# LCD.net
KiCad netlist of a schematic drawn in Altium Designer
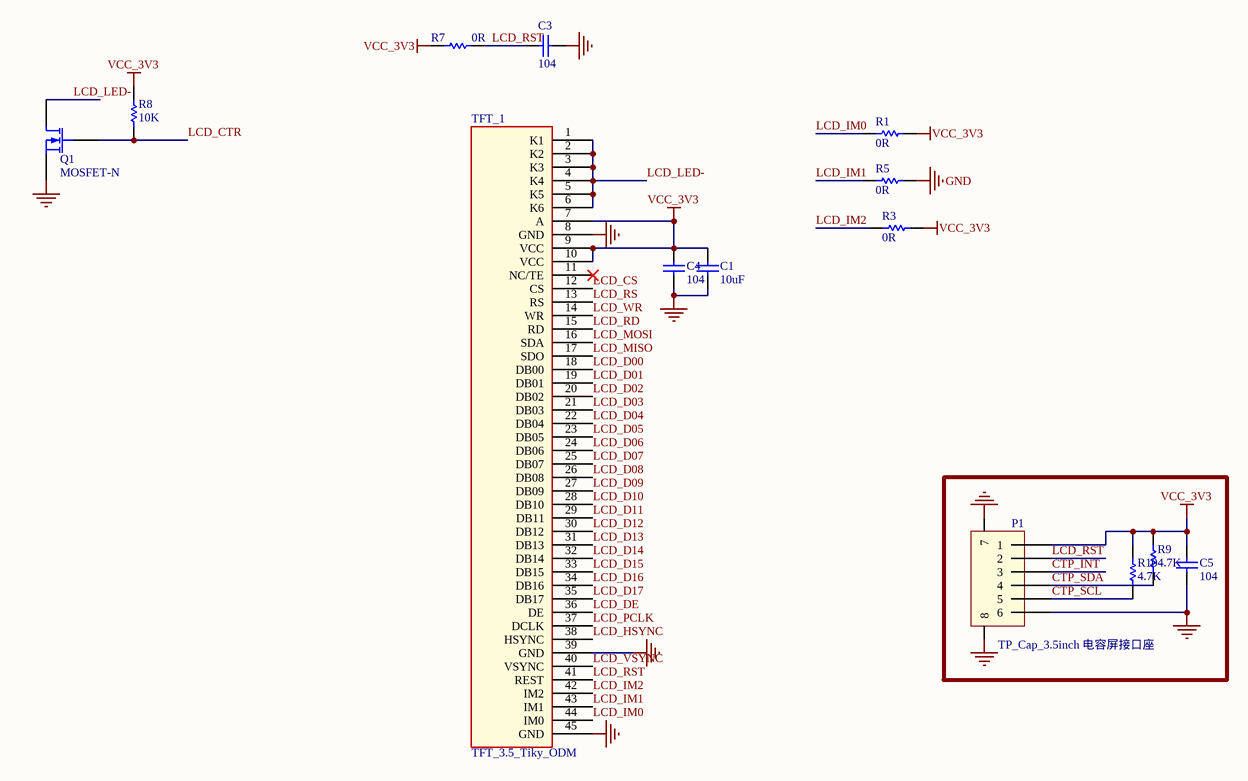
[diagram p0: LCD.SchDoc]

(export (version "E")
  (design (tool "Eeschema 10.0.6"))
  (components
    (comp (ref "C1")
      (value "10uF")
      (footprint "C 0603")
      (description "Capacitor")
      (libsource (lib "Miscellaneous Devices") (part "Cap"))
    )
    (comp (ref "C3") (value "104") (footprint "C 0603") (libsource (lib "Sheet") (part "CAP")))
    (comp (ref "C4")
      (value "104")
      (footprint "C 0603")
      (description "Capacitor")
      (libsource (lib "Miscellaneous Devices") (part "Cap"))
    )
    (comp (ref "C5")
      (value "104")
      (footprint "C 0603")
      (description "Capacitor")
      (libsource (lib "Miscellaneous Devices") (part "Cap"))
    )
    (comp (ref "P1")
      (value "TP_Cap_3.5inch 电容屏接口座")
      (footprint "TP_Cap_3.5inch")
      (libsource (lib "Tiky") (part "BHEADSMD1x6"))
    )
    (comp (ref "Q1") (value "MOSFET-N") (footprint "SOT-23") (libsource (lib "Tiky") (part "MOSFET-N")))
    (comp (ref "R1") (value "0R") (footprint "R 0603") (libsource (lib "Sheet") (part "RES")))
    (comp (ref "R3") (value "0R") (footprint "R 0603") (libsource (lib "Sheet") (part "RES")))
    (comp (ref "R5") (value "0R") (footprint "R 0603") (libsource (lib "Sheet") (part "RES")))
    (comp (ref "R7") (value "0R") (footprint "R 0603") (libsource (lib "Sheet") (part "RES")))
    (comp (ref "R8") (value "10K") (footprint "R 0603") (libsource (lib "Sheet") (part "RES")))
    (comp (ref "R9") (value "4.7K") (footprint "R 0603") (libsource (lib "Sheet") (part "RES")))
    (comp (ref "R10") (value "4.7K") (footprint "R 0603") (libsource (lib "Sheet") (part "RES")))
    (comp (ref "TFT_1")
      (value "TFT_3.5_Tiky_ODM")
      (footprint "TFT_3.5_TIKY_ODM")
      (libsource (lib "Tiky") (part "TFT_3.5_Tiky_ODM"))
    )
  )
  (nets
    (net (code "1") (name "/CTP_INT") (class "Default")
      (node (ref "P1") (pin "3") (pinfunction "3_3") (pintype "passive"))
    )
    (net (code "2") (name "/CTP_SCL") (class "Default")
      (node (ref "P1") (pin "5") (pinfunction "5_5") (pintype "passive"))
      (node (ref "R10") (pin "1") (pinfunction "1_1") (pintype "passive"))
    )
    (net (code "3") (name "/CTP_SDA") (class "Default")
      (node (ref "P1") (pin "4") (pinfunction "4_4") (pintype "passive"))
      (node (ref "R9") (pin "1") (pinfunction "1_1") (pintype "passive"))
    )
    (net (code "4") (name "/LCD_CS") (class "Default")
      (node (ref "TFT_1") (pin "12") (pinfunction "CS_12") (pintype "passive"))
    )
    (net (code "5") (name "/LCD_CTR") (class "Default")
      (node (ref "Q1") (pin "1") (pinfunction "G_1") (pintype "passive"))
      (node (ref "R8") (pin "1") (pinfunction "1_1") (pintype "passive"))
    )
    (net (code "6") (name "/LCD_D00") (class "Default")
      (node (ref "TFT_1") (pin "18") (pinfunction "DB00_18") (pintype "passive"))
    )
    (net (code "7") (name "/LCD_D01") (class "Default")
      (node (ref "TFT_1") (pin "19") (pinfunction "DB01_19") (pintype "passive"))
    )
    (net (code "8") (name "/LCD_D02") (class "Default")
      (node (ref "TFT_1") (pin "20") (pinfunction "DB02_20") (pintype "passive"))
    )
    (net (code "9") (name "/LCD_D03") (class "Default")
      (node (ref "TFT_1") (pin "21") (pinfunction "DB03_21") (pintype "passive"))
    )
    (net (code "10") (name "/LCD_D04") (class "Default")
      (node (ref "TFT_1") (pin "22") (pinfunction "DB04_22") (pintype "passive"))
    )
    (net (code "11") (name "/LCD_D05") (class "Default")
      (node (ref "TFT_1") (pin "23") (pinfunction "DB05_23") (pintype "passive"))
    )
    (net (code "12") (name "/LCD_D06") (class "Default")
      (node (ref "TFT_1") (pin "24") (pinfunction "DB06_24") (pintype "passive"))
    )
    (net (code "13") (name "/LCD_D07") (class "Default")
      (node (ref "TFT_1") (pin "25") (pinfunction "DB07_25") (pintype "passive"))
    )
    (net (code "14") (name "/LCD_D08") (class "Default")
      (node (ref "TFT_1") (pin "26") (pinfunction "DB08_26") (pintype "passive"))
    )
    (net (code "15") (name "/LCD_D09") (class "Default")
      (node (ref "TFT_1") (pin "27") (pinfunction "DB09_27") (pintype "passive"))
    )
    (net (code "16") (name "/LCD_D10") (class "Default")
      (node (ref "TFT_1") (pin "28") (pinfunction "DB10_28") (pintype "passive"))
    )
    (net (code "17") (name "/LCD_D11") (class "Default")
      (node (ref "TFT_1") (pin "29") (pinfunction "DB11_29") (pintype "passive"))
    )
    (net (code "18") (name "/LCD_D12") (class "Default")
      (node (ref "TFT_1") (pin "30") (pinfunction "DB12_30") (pintype "passive"))
    )
    (net (code "19") (name "/LCD_D13") (class "Default")
      (node (ref "TFT_1") (pin "31") (pinfunction "DB13_31") (pintype "passive"))
    )
    (net (code "20") (name "/LCD_D14") (class "Default")
      (node (ref "TFT_1") (pin "32") (pinfunction "DB14_32") (pintype "passive"))
    )
    (net (code "21") (name "/LCD_D15") (class "Default")
      (node (ref "TFT_1") (pin "33") (pinfunction "DB15_33") (pintype "passive"))
    )
    (net (code "22") (name "/LCD_D16") (class "Default")
      (node (ref "TFT_1") (pin "34") (pinfunction "DB16_34") (pintype "passive"))
    )
    (net (code "23") (name "/LCD_D17") (class "Default")
      (node (ref "TFT_1") (pin "35") (pinfunction "DB17_35") (pintype "passive"))
    )
    (net (code "24") (name "/LCD_DE") (class "Default")
      (node (ref "TFT_1") (pin "36") (pinfunction "DE_36") (pintype "passive"))
    )
    (net (code "25") (name "/LCD_HSYNC") (class "Default")
      (node (ref "TFT_1") (pin "38") (pinfunction "HSYNC_38") (pintype "passive"))
    )
    (net (code "26") (name "/LCD_IM0") (class "Default")
      (node (ref "R1") (pin "1") (pinfunction "1_1") (pintype "passive"))
      (node (ref "TFT_1") (pin "44") (pinfunction "IM0_44") (pintype "passive"))
    )
    (net (code "27") (name "/LCD_IM1") (class "Default")
      (node (ref "R5") (pin "1") (pinfunction "1_1") (pintype "passive"))
      (node (ref "TFT_1") (pin "43") (pinfunction "IM1_43") (pintype "passive"))
    )
    (net (code "28") (name "/LCD_IM2") (class "Default")
      (node (ref "R3") (pin "1") (pinfunction "1_1") (pintype "passive"))
      (node (ref "TFT_1") (pin "42") (pinfunction "IM2_42") (pintype "passive"))
    )
    (net (code "29") (name "/LCD_LED-") (class "Default")
      (node (ref "Q1") (pin "3") (pinfunction "D_3") (pintype "passive"))
      (node (ref "TFT_1") (pin "1") (pinfunction "K1_1") (pintype "passive"))
      (node (ref "TFT_1") (pin "2") (pinfunction "K2_2") (pintype "passive"))
      (node (ref "TFT_1") (pin "3") (pinfunction "K3_3") (pintype "passive"))
      (node (ref "TFT_1") (pin "4") (pinfunction "K4_4") (pintype "passive"))
      (node (ref "TFT_1") (pin "5") (pinfunction "K5_5") (pintype "passive"))
      (node (ref "TFT_1") (pin "6") (pinfunction "K6_6") (pintype "passive"))
    )
    (net (code "30") (name "/LCD_MISO") (class "Default")
      (node (ref "TFT_1") (pin "17") (pinfunction "SDO_17") (pintype "passive"))
    )
    (net (code "31") (name "/LCD_MOSI") (class "Default")
      (node (ref "TFT_1") (pin "16") (pinfunction "SDA_16") (pintype "passive"))
    )
    (net (code "32") (name "/LCD_PCLK") (class "Default")
      (node (ref "TFT_1") (pin "37") (pinfunction "DCLK_37") (pintype "passive"))
    )
    (net (code "33") (name "/LCD_RD") (class "Default")
      (node (ref "TFT_1") (pin "15") (pinfunction "RD_15") (pintype "passive"))
    )
    (net (code "34") (name "/LCD_RS") (class "Default")
      (node (ref "TFT_1") (pin "13") (pinfunction "RS_13") (pintype "passive"))
    )
    (net (code "35") (name "/LCD_RST") (class "Default")
      (node (ref "C3") (pin "2") (pinfunction "2_2") (pintype "passive"))
      (node (ref "P1") (pin "2") (pinfunction "2_2") (pintype "passive"))
      (node (ref "R7") (pin "2") (pinfunction "2_2") (pintype "passive"))
      (node (ref "TFT_1") (pin "41") (pinfunction "REST_41") (pintype "passive"))
    )
    (net (code "36") (name "/LCD_VSYNC") (class "Default")
      (node (ref "TFT_1") (pin "40") (pinfunction "VSYNC_40") (pintype "passive"))
    )
    (net (code "37") (name "/LCD_WR") (class "Default")
      (node (ref "TFT_1") (pin "14") (pinfunction "WR_14") (pintype "passive"))
    )
    (net (code "38") (name "GND") (class "Default")
      (node (ref "C1") (pin "2") (pinfunction "2_2") (pintype "passive"))
      (node (ref "C3") (pin "1") (pinfunction "1_1") (pintype "passive"))
      (node (ref "C4") (pin "2") (pinfunction "2_2") (pintype "passive"))
      (node (ref "C5") (pin "2") (pinfunction "2_2") (pintype "passive"))
      (node (ref "P1") (pin "6") (pinfunction "6_6") (pintype "passive"))
      (node (ref "P1") (pin "7") (pinfunction "7_7") (pintype "passive"))
      (node (ref "P1") (pin "8") (pinfunction "8_8") (pintype "passive"))
      (node (ref "Q1") (pin "2") (pinfunction "S_2") (pintype "passive"))
      (node (ref "R5") (pin "2") (pinfunction "2_2") (pintype "passive"))
      (node (ref "TFT_1") (pin "39") (pinfunction "GND_39") (pintype "passive"))
      (node (ref "TFT_1") (pin "45") (pinfunction "GND_45") (pintype "passive"))
      (node (ref "TFT_1") (pin "8") (pinfunction "GND_8") (pintype "passive"))
    )
    (net (code "39") (name "VCC_3V3") (class "Default")
      (node (ref "C1") (pin "1") (pinfunction "1_1") (pintype "passive"))
      (node (ref "C4") (pin "1") (pinfunction "1_1") (pintype "passive"))
      (node (ref "C5") (pin "1") (pinfunction "1_1") (pintype "passive"))
      (node (ref "P1") (pin "1") (pinfunction "1_1") (pintype "passive"))
      (node (ref "R1") (pin "2") (pinfunction "2_2") (pintype "passive"))
      (node (ref "R10") (pin "2") (pinfunction "2_2") (pintype "passive"))
      (node (ref "R3") (pin "2") (pinfunction "2_2") (pintype "passive"))
      (node (ref "R7") (pin "1") (pinfunction "1_1") (pintype "passive"))
      (node (ref "R8") (pin "2") (pinfunction "2_2") (pintype "passive"))
      (node (ref "R9") (pin "2") (pinfunction "2_2") (pintype "passive"))
      (node (ref "TFT_1") (pin "10") (pinfunction "VCC_10") (pintype "passive"))
      (node (ref "TFT_1") (pin "7") (pinfunction "A_7") (pintype "passive"))
      (node (ref "TFT_1") (pin "9") (pinfunction "VCC_9") (pintype "passive"))
    )
    (net (code "40") (name "unconnected-(TFT_1-NC{slash}TE-Pad11)") (class "Default")
      (node (ref "TFT_1") (pin "11") (pinfunction "NC/TE_11") (pintype "passive+no_connect"))
    )
  )
)
